# target.net
KiCad netlist of a schematic drawn in EAGLE
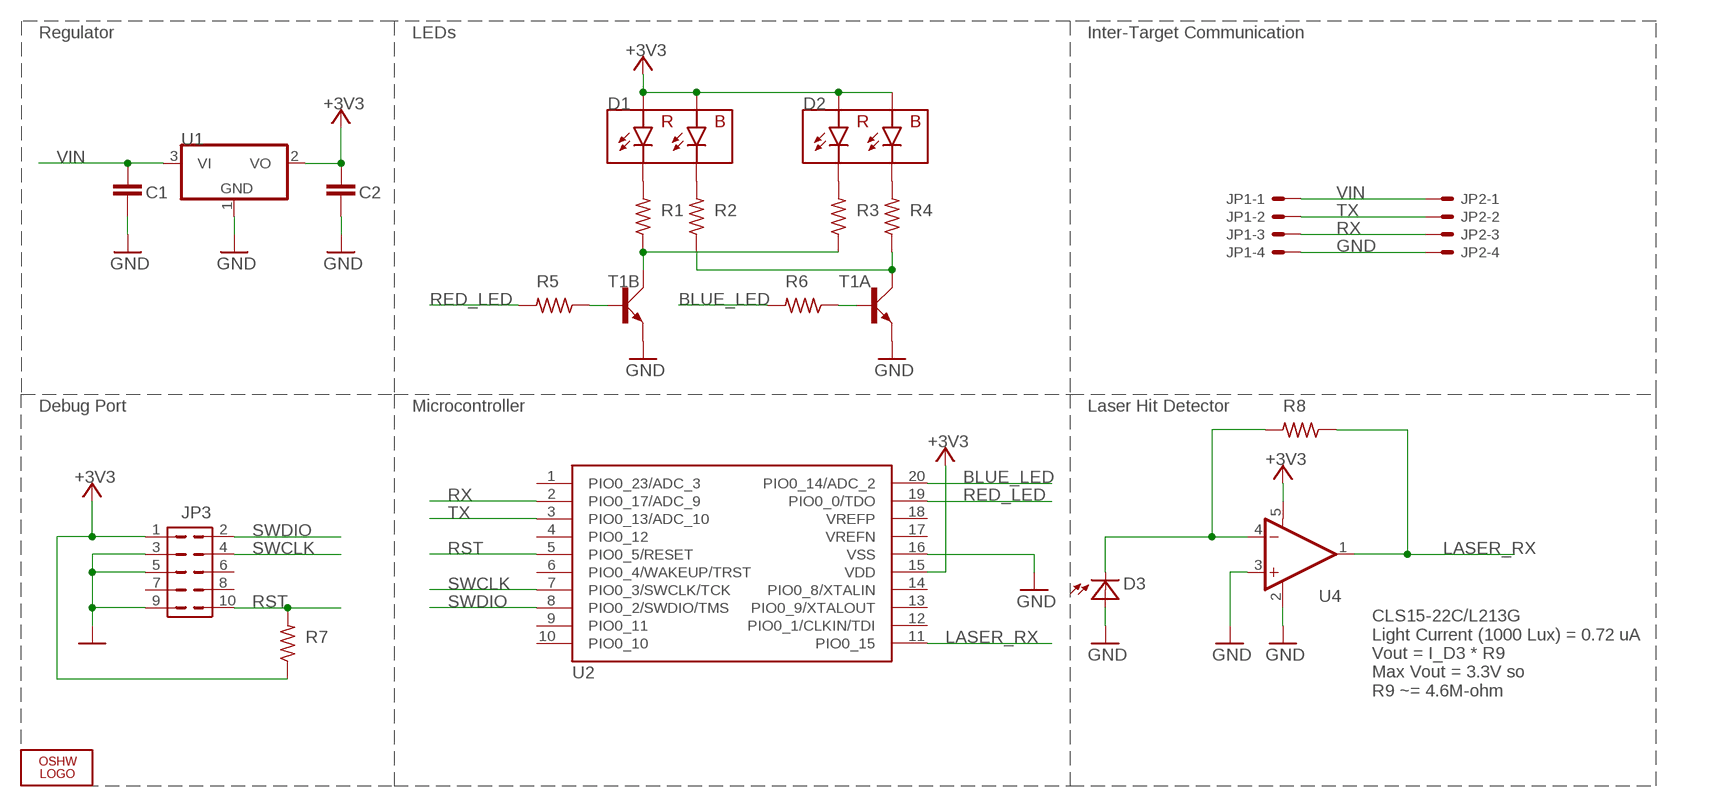
[diagram p0: schematic, sheet 1]

(export (version "E")
  (design (tool "Eeschema 10.0.6"))
  (components
    (comp (ref "C1")
      (value "C1608X5R1C106M080AB")
      (footprint "eagle-import:0603-CAP")
      (libsource (lib "eagle-import") (part "CAP0603-CAP"))
    )
    (comp (ref "C2")
      (value "C1608X5R1C106M080AB")
      (footprint "eagle-import:0603-CAP")
      (libsource (lib "eagle-import") (part "CAP0603-CAP"))
    )
    (comp (ref "D1")
      (value "150141RB73100")
      (footprint "eagle-import:150141RB")
      (libsource (lib "eagle-import") (part "LED_RB"))
    )
    (comp (ref "D2")
      (value "150141RB73100")
      (footprint "eagle-import:150141RB")
      (libsource (lib "eagle-import") (part "LED_RB"))
    )
    (comp (ref "D3")
      (value "638-CLS1522CL213GTR8")
      (footprint "eagle-import:CLS15")
      (libsource (lib "eagle-import") (part "CLS15CLS15"))
    )
    (comp (ref "JP1")
      (value "798-DF134P125V20")
      (footprint "eagle-import:53398-04")
      (libsource (lib "eagle-import") (part "53?-04398"))
    )
    (comp (ref "JP2")
      (value "798-DF134P125V20")
      (footprint "eagle-import:53398-04")
      (libsource (lib "eagle-import") (part "53?-04398"))
    )
    (comp (ref "JP3")
      (value "FTSH-105-01-L")
      (footprint "eagle-import:FTSH-105-01-XXX-DV-K")
      (libsource (lib "eagle-import") (part "FTSH-105"))
    )
    (comp (ref "LOGO2")
      (value "OSHW_LOGO_FILLX0150-NT")
      (footprint "eagle-import:OSHW_FILLX150_NOTEXT")
      (libsource (lib "eagle-import") (part "OSHW_LOGO_FILLX0150-NT"))
    )
    (comp (ref "R1")
      (value "71-CRCW060368R0FKEB")
      (footprint "eagle-import:R0603")
      (libsource (lib "eagle-import") (part "R-US_R0603"))
    )
    (comp (ref "R2")
      (value "71-CRCW0603-5.6-E3")
      (footprint "eagle-import:R0603")
      (libsource (lib "eagle-import") (part "R-US_R0603"))
    )
    (comp (ref "R3")
      (value "71-CRCW060368R0FKEB")
      (footprint "eagle-import:R0603")
      (libsource (lib "eagle-import") (part "R-US_R0603"))
    )
    (comp (ref "R4")
      (value "71-CRCW0603-5.6-E3")
      (footprint "eagle-import:R0603")
      (libsource (lib "eagle-import") (part "R-US_R0603"))
    )
    (comp (ref "R5")
      (value "71-CRCW0603220RFKEB")
      (footprint "eagle-import:R0603")
      (libsource (lib "eagle-import") (part "R-US_R0603"))
    )
    (comp (ref "R6")
      (value "71-CRCW0603220RFKEB")
      (footprint "eagle-import:R0603")
      (libsource (lib "eagle-import") (part "R-US_R0603"))
    )
    (comp (ref "R7")
      (value "71-CRCW0603-10K-E3")
      (footprint "eagle-import:R0603")
      (libsource (lib "eagle-import") (part "R-US_R0603"))
    )
    (comp (ref "R8")
      (value "71-CRCW06034M64FKEA")
      (footprint "eagle-import:R0603")
      (libsource (lib "eagle-import") (part "R-US_R0603"))
    )
    (comp (ref "T1")
      (value "771-BC847BS-T/R")
      (footprint "eagle-import:SOT363_PHILIPS")
      (libsource (lib "eagle-import") (part "BC847BS"))
    )
    (comp (ref "U1")
      (value "579-MCP1703T-3002ECB")
      (footprint "eagle-import:SOT23")
      (libsource (lib "eagle-import") (part "MCP1703CB"))
    )
    (comp (ref "U2")
      (value "771-LPC824M201JDH20J")
      (footprint "eagle-import:TSSOP20")
      (libsource (lib "eagle-import") (part "LPC824"))
    )
    (comp (ref "U4")
      (value "579-MCP6291T-E/OT")
      (footprint "eagle-import:SOT23-5")
      (libsource (lib "eagle-import") (part "MCP6291T-E/OT"))
    )
  )
  (nets
    (net (code "1") (name "+3V3") (class "Default")
      (node (ref "C2") (pin "1") (pinfunction "1_1") (pintype "passive"))
      (node (ref "D1") (pin "1") (pinfunction "1_1") (pintype "passive"))
      (node (ref "D1") (pin "2") (pinfunction "2_2") (pintype "passive"))
      (node (ref "D2") (pin "1") (pinfunction "1_1") (pintype "passive"))
      (node (ref "D2") (pin "2") (pinfunction "2_2") (pintype "passive"))
      (node (ref "JP3") (pin "1") (pinfunction "1_1") (pintype "passive"))
      (node (ref "R7") (pin "1") (pinfunction "1_1") (pintype "passive"))
      (node (ref "U1") (pin "2") (pinfunction "VO_2") (pintype "passive"))
      (node (ref "U2") (pin "15") (pinfunction "VDD_15") (pintype "bidirectional"))
      (node (ref "U4") (pin "5") (pinfunction "V+_5") (pintype "power_in"))
    )
    (net (code "2") (name "/BLUE_LED") (class "Default")
      (node (ref "R6") (pin "2") (pinfunction "2_2") (pintype "passive"))
      (node (ref "U2") (pin "20") (pinfunction "PIO0_14/ADC_2_20") (pintype "bidirectional"))
    )
    (net (code "3") (name "/LASER_RX") (class "Default")
      (node (ref "R8") (pin "1") (pinfunction "1_1") (pintype "passive"))
      (node (ref "U2") (pin "11") (pinfunction "PIO0_15_11") (pintype "bidirectional"))
      (node (ref "U4") (pin "1") (pinfunction "OUT_1") (pintype "output"))
    )
    (net (code "4") (name "/RED_LED") (class "Default")
      (node (ref "R5") (pin "2") (pinfunction "2_2") (pintype "passive"))
      (node (ref "U2") (pin "19") (pinfunction "PIO0_0/TDO_19") (pintype "bidirectional"))
    )
    (net (code "5") (name "/RST") (class "Default")
      (node (ref "JP3") (pin "10") (pinfunction "10_10") (pintype "passive"))
      (node (ref "R7") (pin "2") (pinfunction "2_2") (pintype "passive"))
      (node (ref "U2") (pin "5") (pinfunction "PIO0_5/RESET_5") (pintype "bidirectional"))
    )
    (net (code "6") (name "/RX") (class "Default")
      (node (ref "JP1") (pin "3") (pinfunction "S_3") (pintype "passive"))
      (node (ref "JP2") (pin "3") (pinfunction "S_3") (pintype "passive"))
      (node (ref "U2") (pin "2") (pinfunction "PIO0_17/ADC_9_2") (pintype "bidirectional"))
    )
    (net (code "7") (name "/SWCLK") (class "Default")
      (node (ref "JP3") (pin "4") (pinfunction "4_4") (pintype "passive"))
      (node (ref "U2") (pin "7") (pinfunction "PIO0_3/SWCLK/TCK_7") (pintype "bidirectional"))
    )
    (net (code "8") (name "/SWDIO") (class "Default")
      (node (ref "JP3") (pin "2") (pinfunction "2_2") (pintype "passive"))
      (node (ref "U2") (pin "8") (pinfunction "PIO0_2/SWDIO/TMS_8") (pintype "bidirectional"))
    )
    (net (code "9") (name "/TX") (class "Default")
      (node (ref "JP1") (pin "2") (pinfunction "S_2") (pintype "passive"))
      (node (ref "JP2") (pin "2") (pinfunction "S_2") (pintype "passive"))
      (node (ref "U2") (pin "3") (pinfunction "PIO0_13/ADC_10_3") (pintype "bidirectional"))
    )
    (net (code "10") (name "/VIN") (class "Default")
      (node (ref "C1") (pin "1") (pinfunction "1_1") (pintype "passive"))
      (node (ref "JP1") (pin "1") (pinfunction "S_1") (pintype "passive"))
      (node (ref "JP2") (pin "1") (pinfunction "S_1") (pintype "passive"))
      (node (ref "U1") (pin "3") (pinfunction "VI_3") (pintype "input"))
    )
    (net (code "11") (name "GND") (class "Default")
      (node (ref "C1") (pin "2") (pinfunction "2_2") (pintype "passive"))
      (node (ref "C2") (pin "2") (pinfunction "2_2") (pintype "passive"))
      (node (ref "D3") (pin "1") (pinfunction "A_1") (pintype "passive"))
      (node (ref "D3") (pin "2") (pinfunction "A_2") (pintype "passive"))
      (node (ref "JP1") (pin "4") (pinfunction "S_4") (pintype "passive"))
      (node (ref "JP2") (pin "4") (pinfunction "S_4") (pintype "passive"))
      (node (ref "JP3") (pin "3") (pinfunction "3_3") (pintype "passive"))
      (node (ref "JP3") (pin "5") (pinfunction "5_5") (pintype "passive"))
      (node (ref "JP3") (pin "9") (pinfunction "9_9") (pintype "passive"))
      (node (ref "T1") (pin "1") (pinfunction "E_1") (pintype "passive"))
      (node (ref "T1") (pin "4") (pinfunction "E_4") (pintype "passive"))
      (node (ref "U1") (pin "1") (pinfunction "GND_1") (pintype "passive"))
      (node (ref "U2") (pin "16") (pinfunction "VSS_16") (pintype "bidirectional"))
      (node (ref "U4") (pin "2") (pinfunction "V-_2") (pintype "power_in"))
      (node (ref "U4") (pin "3") (pinfunction "+IN_3") (pintype "input"))
    )
    (net (code "12") (name "Net-(D1-Pad3)") (class "Default")
      (node (ref "D1") (pin "3") (pinfunction "3_3") (pintype "passive"))
      (node (ref "R1") (pin "2") (pinfunction "2_2") (pintype "passive"))
    )
    (net (code "13") (name "Net-(D1-Pad4)") (class "Default")
      (node (ref "D1") (pin "4") (pinfunction "4_4") (pintype "passive"))
      (node (ref "R2") (pin "2") (pinfunction "2_2") (pintype "passive"))
    )
    (net (code "14") (name "Net-(D2-Pad3)") (class "Default")
      (node (ref "D2") (pin "3") (pinfunction "3_3") (pintype "passive"))
      (node (ref "R3") (pin "2") (pinfunction "2_2") (pintype "passive"))
    )
    (net (code "15") (name "Net-(D2-Pad4)") (class "Default")
      (node (ref "D2") (pin "4") (pinfunction "4_4") (pintype "passive"))
      (node (ref "R4") (pin "2") (pinfunction "2_2") (pintype "passive"))
    )
    (net (code "16") (name "Net-(T1A-B)") (class "Default")
      (node (ref "R6") (pin "1") (pinfunction "1_1") (pintype "passive"))
      (node (ref "T1") (pin "2") (pinfunction "B_2") (pintype "passive"))
    )
    (net (code "17") (name "Net-(T1A-C)") (class "Default")
      (node (ref "R2") (pin "1") (pinfunction "1_1") (pintype "passive"))
      (node (ref "R4") (pin "1") (pinfunction "1_1") (pintype "passive"))
      (node (ref "T1") (pin "6") (pinfunction "C_6") (pintype "passive"))
    )
    (net (code "18") (name "Net-(T1B-B)") (class "Default")
      (node (ref "R5") (pin "1") (pinfunction "1_1") (pintype "passive"))
      (node (ref "T1") (pin "5") (pinfunction "B_5") (pintype "passive"))
    )
    (net (code "19") (name "Net-(T1B-C)") (class "Default")
      (node (ref "R1") (pin "1") (pinfunction "1_1") (pintype "passive"))
      (node (ref "R3") (pin "1") (pinfunction "1_1") (pintype "passive"))
      (node (ref "T1") (pin "3") (pinfunction "C_3") (pintype "passive"))
    )
    (net (code "20") (name "Net-(U4--IN)") (class "Default")
      (node (ref "D3") (pin "3") (pinfunction "C_3") (pintype "passive"))
      (node (ref "D3") (pin "4") (pinfunction "C_4") (pintype "passive"))
      (node (ref "R8") (pin "2") (pinfunction "2_2") (pintype "passive"))
      (node (ref "U4") (pin "4") (pinfunction "-IN_4") (pintype "input"))
    )
    (net (code "21") (name "unconnected-(JP3-Pad6)") (class "Default")
      (node (ref "JP3") (pin "6") (pinfunction "6_6") (pintype "passive"))
    )
    (net (code "22") (name "unconnected-(JP3-Pad7)") (class "Default")
      (node (ref "JP3") (pin "7") (pinfunction "7_7") (pintype "passive"))
    )
    (net (code "23") (name "unconnected-(JP3-Pad8)") (class "Default")
      (node (ref "JP3") (pin "8") (pinfunction "8_8") (pintype "passive"))
    )
    (net (code "24") (name "unconnected-(U2-PIO0_1{slash}CLKIN{slash}TDI-Pad12)") (class "Default")
      (node (ref "U2") (pin "12") (pinfunction "PIO0_1/CLKIN/TDI_12") (pintype "bidirectional"))
    )
    (net (code "25") (name "unconnected-(U2-PIO0_4{slash}WAKEUP{slash}TRST-Pad6)") (class "Default")
      (node (ref "U2") (pin "6") (pinfunction "PIO0_4/WAKEUP/TRST_6") (pintype "bidirectional"))
    )
    (net (code "26") (name "unconnected-(U2-PIO0_8{slash}XTALIN-Pad14)") (class "Default")
      (node (ref "U2") (pin "14") (pinfunction "PIO0_8/XTALIN_14") (pintype "bidirectional"))
    )
    (net (code "27") (name "unconnected-(U2-PIO0_9{slash}XTALOUT-Pad13)") (class "Default")
      (node (ref "U2") (pin "13") (pinfunction "PIO0_9/XTALOUT_13") (pintype "bidirectional"))
    )
    (net (code "28") (name "unconnected-(U2-PIO0_10-Pad10)") (class "Default")
      (node (ref "U2") (pin "10") (pinfunction "PIO0_10_10") (pintype "bidirectional"))
    )
    (net (code "29") (name "unconnected-(U2-PIO0_11-Pad9)") (class "Default")
      (node (ref "U2") (pin "9") (pinfunction "PIO0_11_9") (pintype "bidirectional"))
    )
    (net (code "30") (name "unconnected-(U2-PIO0_12-Pad4)") (class "Default")
      (node (ref "U2") (pin "4") (pinfunction "PIO0_12_4") (pintype "bidirectional"))
    )
    (net (code "31") (name "unconnected-(U2-PIO0_23{slash}ADC_3-Pad1)") (class "Default")
      (node (ref "U2") (pin "1") (pinfunction "PIO0_23/ADC_3_1") (pintype "bidirectional"))
    )
    (net (code "32") (name "unconnected-(U2-VREFN-Pad17)") (class "Default")
      (node (ref "U2") (pin "17") (pinfunction "VREFN_17") (pintype "bidirectional"))
    )
    (net (code "33") (name "unconnected-(U2-VREFP-Pad18)") (class "Default")
      (node (ref "U2") (pin "18") (pinfunction "VREFP_18") (pintype "bidirectional"))
    )
  )
)
